# FPGA_MGT.net
KiCad netlist of a schematic drawn in Altium Designer
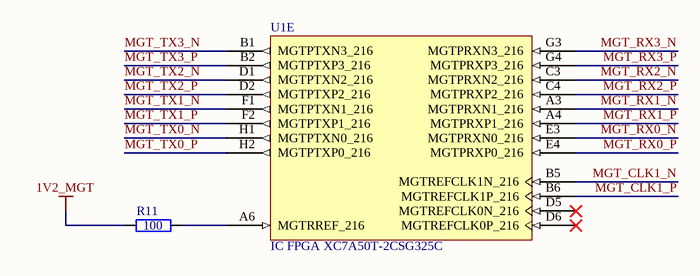
[diagram p0: FPGA_MGT.SchDoc]

(export (version "E")
  (design (tool "Eeschema 10.0.6"))
  (components
    (comp (ref "R11")
      (value "100")
      (footprint "GEN_R_0201")
      (fields
        (field (name "TOLERANCE") "1%")
        (field (name "HOUSE PART NUMBER") "R-100-0201-1%-001")
        (field (name "MANUFACTURER") "Yageo")
      )
      (libsource (lib "DSO") (part "RES 100 OHM 1% 1/20W 0201"))
    )
    (comp (ref "U1")
      (value "IC FPGA XC7A50T-2CSG325C")
      (footprint "XILINX_XC7A50T-2CSG325C")
      (description "Artix-7 FPGA, 150 User I/Os, 4 GTP, 324-Ball BGA, Speed Grade 2, Commercial Grade, Pb-Free")
      (fields (field (name "MANUFACTURER") "Xilinx") (field (name "HOUSE PART NUMBER") "XC7A50T-2CSG325C"))
      (libsource (lib "DSO") (part "IC FPGA XC7A50T-2CSG325C"))
    )
  )
  (nets
    (net (code "1") (name "/MGT_CLK1_N") (class "Default")
      (node (ref "U1") (pin "B5") (pinfunction "MGTREFCLK1N_216_B5") (pintype "input"))
    )
    (net (code "2") (name "/MGT_CLK1_P") (class "Default")
      (node (ref "U1") (pin "B6") (pinfunction "MGTREFCLK1P_216_B6") (pintype "input"))
    )
    (net (code "3") (name "/MGT_RX0_N") (class "Default")
      (node (ref "U1") (pin "E3") (pinfunction "MGTPRXN0_216_E3") (pintype "input"))
    )
    (net (code "4") (name "/MGT_RX0_P") (class "Default")
      (node (ref "U1") (pin "E4") (pinfunction "MGTPRXP0_216_E4") (pintype "input"))
    )
    (net (code "5") (name "/MGT_RX1_N") (class "Default")
      (node (ref "U1") (pin "A3") (pinfunction "MGTPRXN1_216_A3") (pintype "input"))
    )
    (net (code "6") (name "/MGT_RX1_P") (class "Default")
      (node (ref "U1") (pin "A4") (pinfunction "MGTPRXP1_216_A4") (pintype "input"))
    )
    (net (code "7") (name "/MGT_RX2_N") (class "Default")
      (node (ref "U1") (pin "C3") (pinfunction "MGTPRXN2_216_C3") (pintype "input"))
    )
    (net (code "8") (name "/MGT_RX2_P") (class "Default")
      (node (ref "U1") (pin "C4") (pinfunction "MGTPRXP2_216_C4") (pintype "input"))
    )
    (net (code "9") (name "/MGT_RX3_N") (class "Default")
      (node (ref "U1") (pin "G3") (pinfunction "MGTPRXN3_216_G3") (pintype "input"))
    )
    (net (code "10") (name "/MGT_RX3_P") (class "Default")
      (node (ref "U1") (pin "G4") (pinfunction "MGTPRXP3_216_G4") (pintype "input"))
    )
    (net (code "11") (name "/MGT_TX0_N") (class "Default")
      (node (ref "U1") (pin "H1") (pinfunction "MGTPTXN0_216_H1") (pintype "output"))
    )
    (net (code "12") (name "/MGT_TX0_P") (class "Default")
      (node (ref "U1") (pin "H2") (pinfunction "MGTPTXP0_216_H2") (pintype "output"))
    )
    (net (code "13") (name "/MGT_TX1_N") (class "Default")
      (node (ref "U1") (pin "F1") (pinfunction "MGTPTXN1_216_F1") (pintype "output"))
    )
    (net (code "14") (name "/MGT_TX1_P") (class "Default")
      (node (ref "U1") (pin "F2") (pinfunction "MGTPTXP1_216_F2") (pintype "output"))
    )
    (net (code "15") (name "/MGT_TX2_N") (class "Default")
      (node (ref "U1") (pin "D1") (pinfunction "MGTPTXN2_216_D1") (pintype "output"))
    )
    (net (code "16") (name "/MGT_TX2_P") (class "Default")
      (node (ref "U1") (pin "D2") (pinfunction "MGTPTXP2_216_D2") (pintype "output"))
    )
    (net (code "17") (name "/MGT_TX3_N") (class "Default")
      (node (ref "U1") (pin "B1") (pinfunction "MGTPTXN3_216_B1") (pintype "output"))
    )
    (net (code "18") (name "/MGT_TX3_P") (class "Default")
      (node (ref "U1") (pin "B2") (pinfunction "MGTPTXP3_216_B2") (pintype "output"))
    )
    (net (code "19") (name "1V2_MGT") (class "Default")
      (node (ref "R11") (pin "1") (pinfunction "1_1") (pintype "passive"))
    )
    (net (code "20") (name "Net-(U1E-MGTRREF_216)") (class "Default")
      (node (ref "R11") (pin "2") (pinfunction "2_2") (pintype "passive"))
      (node (ref "U1") (pin "A6") (pinfunction "MGTRREF_216_A6") (pintype "input"))
    )
    (net (code "21") (name "unconnected-(U1E-MGTREFCLK0N_216-PadD5)") (class "Default")
      (node (ref "U1") (pin "D5") (pinfunction "MGTREFCLK0N_216_D5") (pintype "input+no_connect"))
    )
    (net (code "22") (name "unconnected-(U1E-MGTREFCLK0P_216-PadD6)") (class "Default")
      (node (ref "U1") (pin "D6") (pinfunction "MGTREFCLK0P_216_D6") (pintype "input+no_connect"))
    )
  )
)
